# PY32.net
KiCad netlist of a schematic drawn in EasyEDA Pro
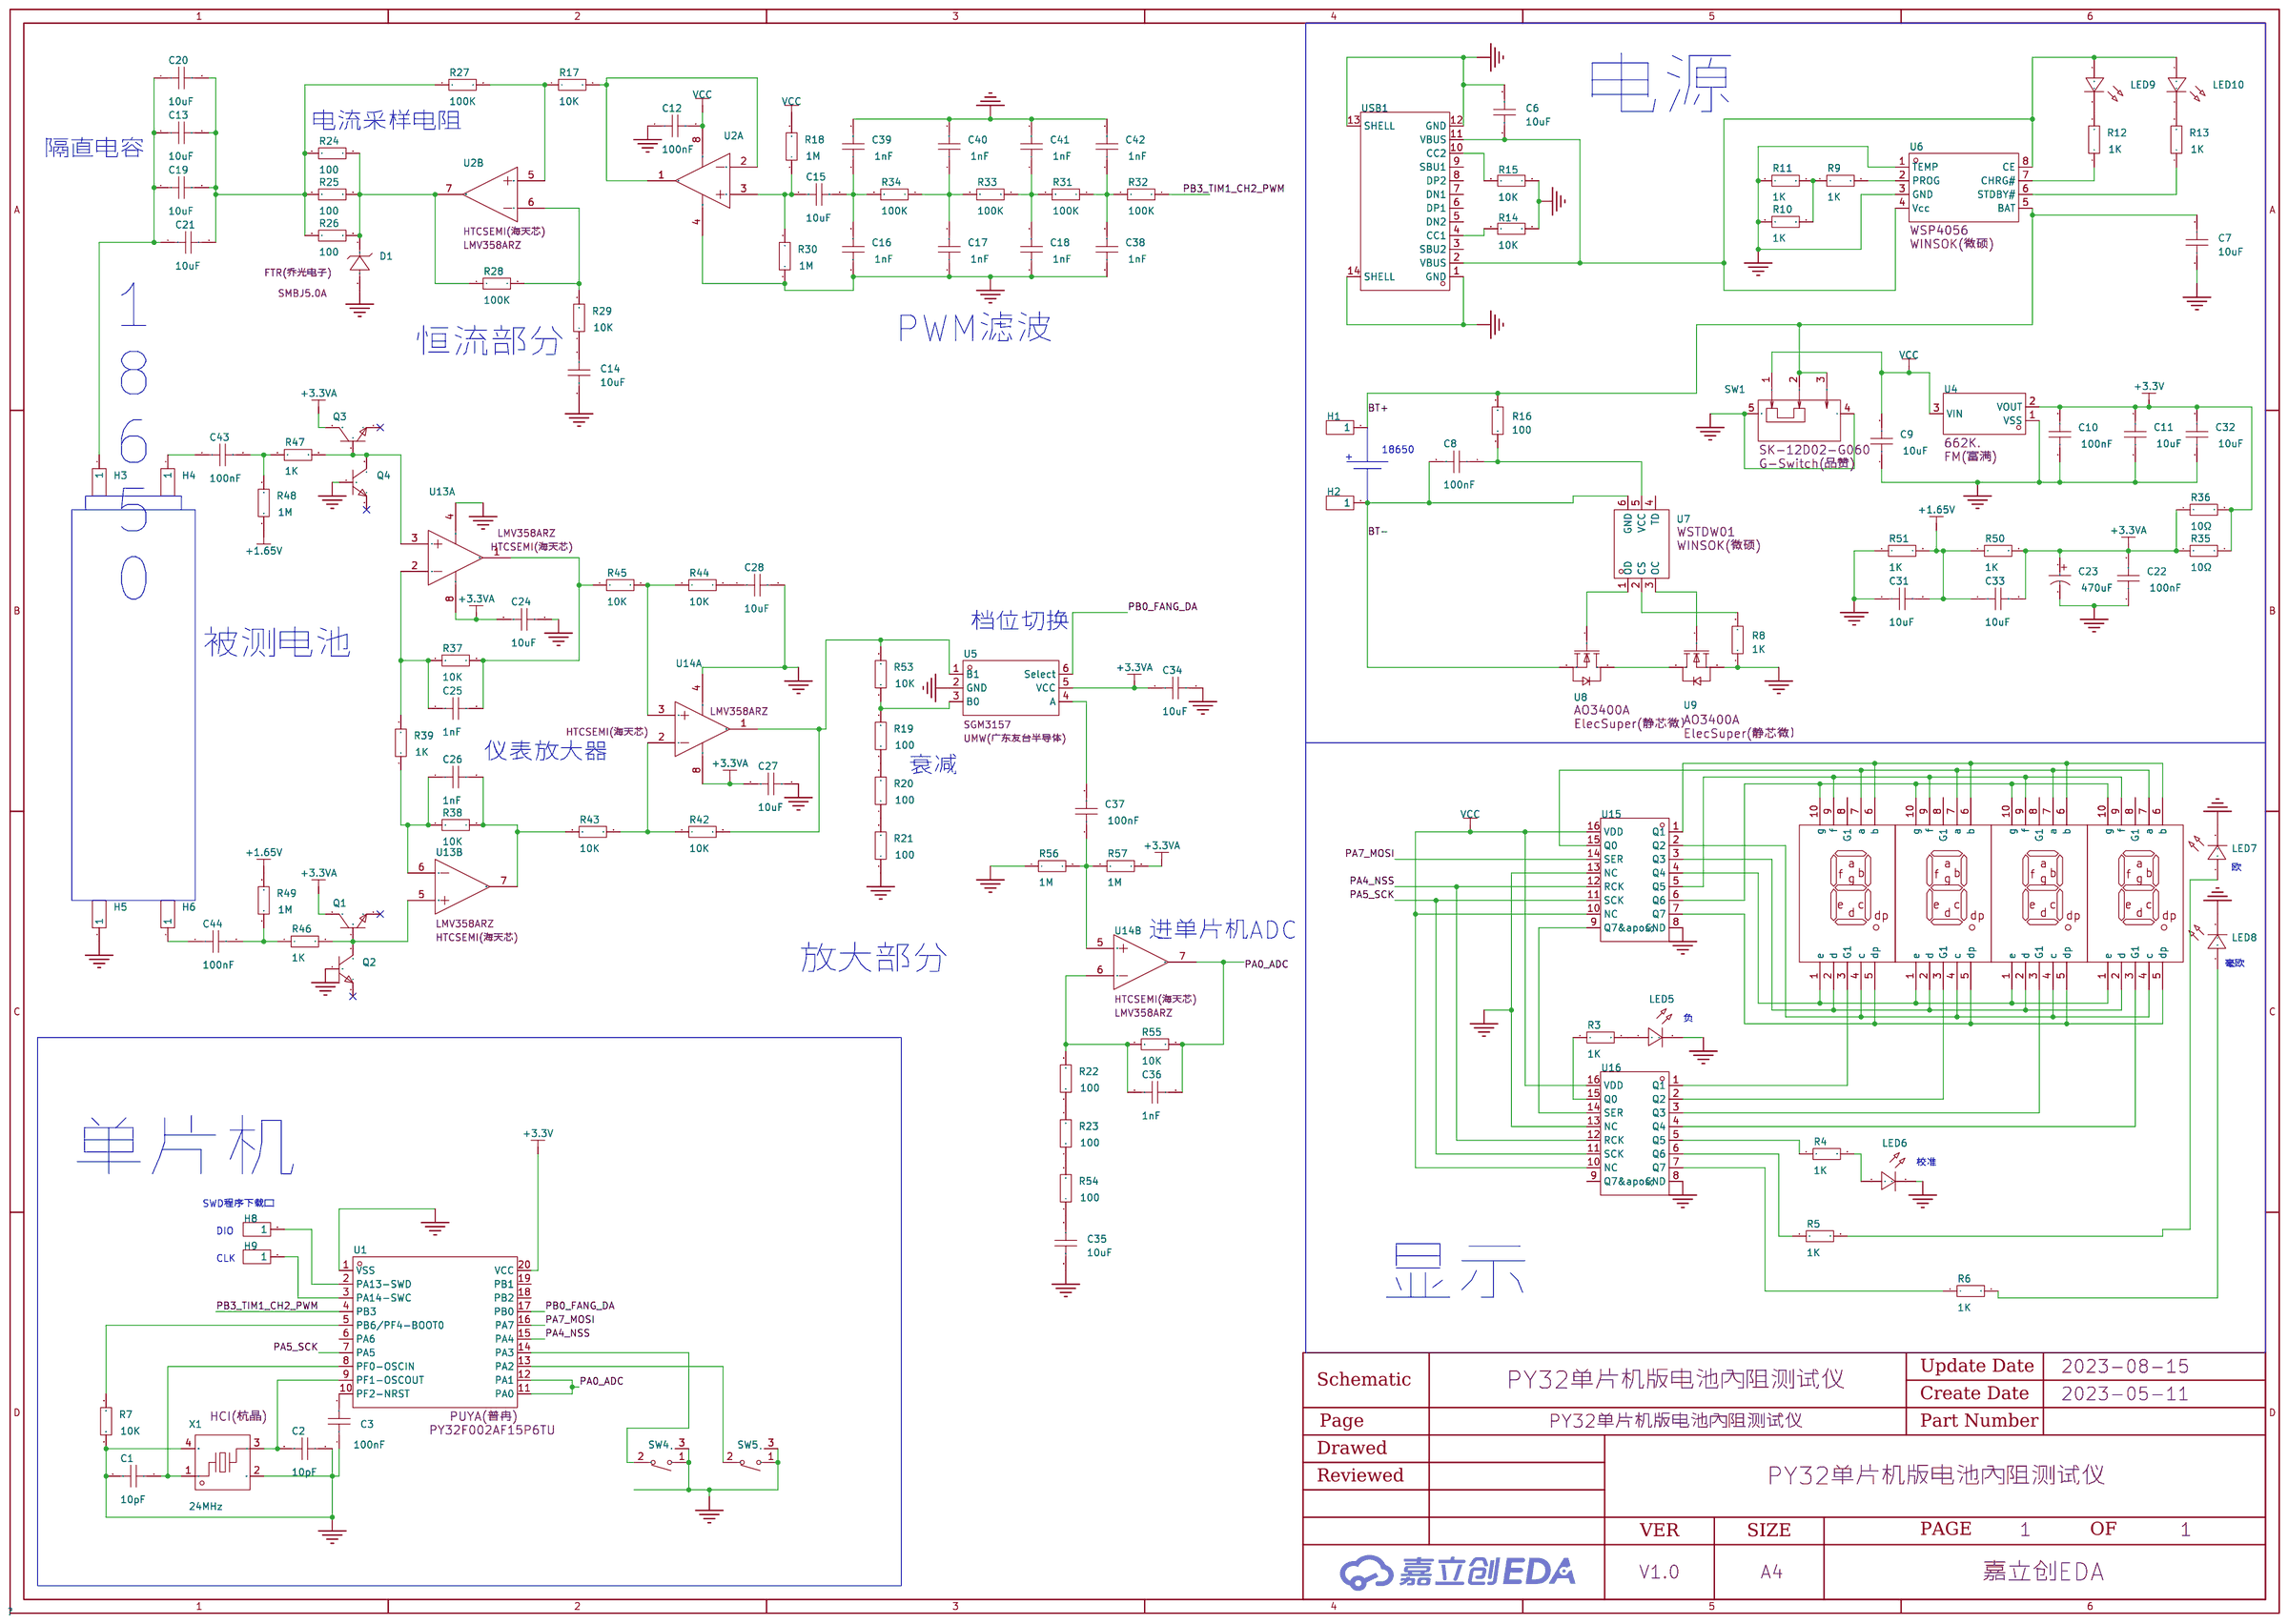
[diagram p0: schematic sheet]

(export (version "E")
  (design (tool "Eeschema 10.0.6"))
  (components
    (comp (ref "C1")
      (value "10pF")
      (footprint "easyedapro:C0603")
      (libsource (lib "easyedapro") (part "CapAcitance"))
    )
    (comp (ref "C2")
      (value "10pF")
      (footprint "easyedapro:C0603")
      (libsource (lib "easyedapro") (part "CapAcitance"))
    )
    (comp (ref "C3")
      (value "100nF")
      (footprint "easyedapro:C0603")
      (libsource (lib "easyedapro") (part "CapAcitance"))
    )
    (comp (ref "C6")
      (value "10uF")
      (footprint "easyedapro:C0603")
      (libsource (lib "easyedapro") (part "CapAcitance"))
    )
    (comp (ref "C7")
      (value "10uF")
      (footprint "easyedapro:C0603")
      (libsource (lib "easyedapro") (part "CapAcitance"))
    )
    (comp (ref "C8")
      (value "100nF")
      (footprint "easyedapro:C0603")
      (libsource (lib "easyedapro") (part "CapAcitance"))
    )
    (comp (ref "C9")
      (value "10uF")
      (footprint "easyedapro:C0603")
      (libsource (lib "easyedapro") (part "CapAcitance"))
    )
    (comp (ref "C10")
      (value "100nF")
      (footprint "easyedapro:C0603")
      (libsource (lib "easyedapro") (part "CapAcitance"))
    )
    (comp (ref "C11")
      (value "10uF")
      (footprint "easyedapro:C0603")
      (libsource (lib "easyedapro") (part "CapAcitance"))
    )
    (comp (ref "C12")
      (value "100nF")
      (footprint "easyedapro:C0603")
      (libsource (lib "easyedapro") (part "CapAcitance"))
    )
    (comp (ref "C13")
      (value "10uF")
      (footprint "easyedapro:C0603")
      (libsource (lib "easyedapro") (part "CapAcitance"))
    )
    (comp (ref "C14")
      (value "10uF")
      (footprint "easyedapro:C0603")
      (libsource (lib "easyedapro") (part "CapAcitance"))
    )
    (comp (ref "C15")
      (value "10uF")
      (footprint "easyedapro:C0603")
      (libsource (lib "easyedapro") (part "CapAcitance"))
    )
    (comp (ref "C16")
      (value "1nF")
      (footprint "easyedapro:C0603")
      (libsource (lib "easyedapro") (part "CapAcitance"))
    )
    (comp (ref "C17")
      (value "1nF")
      (footprint "easyedapro:C0603")
      (libsource (lib "easyedapro") (part "CapAcitance"))
    )
    (comp (ref "C18")
      (value "1nF")
      (footprint "easyedapro:C0603")
      (libsource (lib "easyedapro") (part "CapAcitance"))
    )
    (comp (ref "C19")
      (value "10uF")
      (footprint "easyedapro:C0603")
      (libsource (lib "easyedapro") (part "CapAcitance"))
    )
    (comp (ref "C20")
      (value "10uF")
      (footprint "easyedapro:C0603")
      (libsource (lib "easyedapro") (part "CapAcitance"))
    )
    (comp (ref "C21")
      (value "10uF")
      (footprint "easyedapro:C0603")
      (libsource (lib "easyedapro") (part "CapAcitance"))
    )
    (comp (ref "C22")
      (value "100nF")
      (footprint "easyedapro:C0603")
      (libsource (lib "easyedapro") (part "CapAcitance"))
    )
    (comp (ref "C23")
      (value "470uF")
      (footprint "easyedapro:CAP-TH_BD8.0-P3.50-D0.6-FD")
      (description "容值:470uF;精度:±20%;额定电压:16V;")
      (fields
        (field (name "Manufacturer Part") "KM477M016F12RR0VH2FP0")
        (field (name "Manufacturer") "CX(承兴)")
      )
      (libsource (lib "easyedapro") (part "470uf16v"))
    )
    (comp (ref "C24")
      (value "10uF")
      (footprint "easyedapro:C0603")
      (libsource (lib "easyedapro") (part "CapAcitance"))
    )
    (comp (ref "C25")
      (value "1nF")
      (footprint "easyedapro:C0603")
      (libsource (lib "easyedapro") (part "CapAcitance"))
    )
    (comp (ref "C26")
      (value "1nF")
      (footprint "easyedapro:C0603")
      (libsource (lib "easyedapro") (part "CapAcitance"))
    )
    (comp (ref "C27")
      (value "10uF")
      (footprint "easyedapro:C0603")
      (libsource (lib "easyedapro") (part "CapAcitance"))
    )
    (comp (ref "C28")
      (value "10uF")
      (footprint "easyedapro:C0603")
      (libsource (lib "easyedapro") (part "CapAcitance"))
    )
    (comp (ref "C31")
      (value "10uF")
      (footprint "easyedapro:C0603")
      (libsource (lib "easyedapro") (part "CapAcitance"))
    )
    (comp (ref "C32")
      (value "10uF")
      (footprint "easyedapro:C0603")
      (libsource (lib "easyedapro") (part "CapAcitance"))
    )
    (comp (ref "C33")
      (value "10uF")
      (footprint "easyedapro:C0603")
      (libsource (lib "easyedapro") (part "CapAcitance"))
    )
    (comp (ref "C34")
      (value "10uF")
      (footprint "easyedapro:C0603")
      (libsource (lib "easyedapro") (part "CapAcitance"))
    )
    (comp (ref "C35")
      (value "10uF")
      (footprint "easyedapro:C0603")
      (libsource (lib "easyedapro") (part "CapAcitance"))
    )
    (comp (ref "C36")
      (value "1nF")
      (footprint "easyedapro:C0603")
      (libsource (lib "easyedapro") (part "CapAcitance"))
    )
    (comp (ref "C37")
      (value "100nF")
      (footprint "easyedapro:C0603")
      (libsource (lib "easyedapro") (part "CapAcitance"))
    )
    (comp (ref "C38")
      (value "1nF")
      (footprint "easyedapro:C0603")
      (libsource (lib "easyedapro") (part "CapAcitance"))
    )
    (comp (ref "C39")
      (value "1nF")
      (footprint "easyedapro:C0603")
      (libsource (lib "easyedapro") (part "CapAcitance"))
    )
    (comp (ref "C40")
      (value "1nF")
      (footprint "easyedapro:C0603")
      (libsource (lib "easyedapro") (part "CapAcitance"))
    )
    (comp (ref "C41")
      (value "1nF")
      (footprint "easyedapro:C0603")
      (libsource (lib "easyedapro") (part "CapAcitance"))
    )
    (comp (ref "C42")
      (value "1nF")
      (footprint "easyedapro:C0603")
      (libsource (lib "easyedapro") (part "CapAcitance"))
    )
    (comp (ref "C43")
      (value "100nF")
      (footprint "easyedapro:C1206")
      (description "容值:100nF;精度:±10%;额定电压:450V;材质(温度系数):X7R;")
      (fields (field (name "Manufacturer Part") "FM31X104K451EEG") (field (name "Manufacturer") "PSA(信昌电陶)"))
      (libsource (lib "easyedapro") (part "FM31X104K451EEG"))
    )
    (comp (ref "C44")
      (value "100nF")
      (footprint "easyedapro:C1206")
      (description "容值:100nF;精度:±10%;额定电压:450V;材质(温度系数):X7R;")
      (fields (field (name "Manufacturer Part") "FM31X104K451EEG") (field (name "Manufacturer") "PSA(信昌电陶)"))
      (libsource (lib "easyedapro") (part "FM31X104K451EEG"))
    )
    (comp (ref "D1")
      (value "SMBJ5.0A")
      (footprint "easyedapro:SMB_L4.3-W3.6-LS5.3-RD")
      (description "极性:单向;反向截止电压(Vrwm):5V;击穿电压(最小值):6.4V;峰值脉冲电流(Ipp)@10/1000s:65.3A;最大钳位电压:9.2V;")
      (fields (field (name "Manufacturer Part") "SMBJ5.0A") (field (name "Manufacturer") "FTR(乔光电子)"))
      (libsource (lib "easyedapro") (part "SMBJ5.0A_C693503"))
    )
    (comp (ref "H1")
      (value "~")
      (footprint "easyedapro:HDR-TH_1P-V-M_XKB_X4611WV-01I-C28D40")
      (libsource (lib "easyedapro") (part "HDR_1x1"))
    )
    (comp (ref "H2")
      (value "~")
      (footprint "easyedapro:HDR-TH_1P-V-M_XKB_X4611WV-01I-C28D40")
      (libsource (lib "easyedapro") (part "HDR_1x1"))
    )
    (comp (ref "H3")
      (value "~")
      (footprint "easyedapro:HDR-TH_1P-V-M_XKB_X4611WV-01I-C28D40")
      (libsource (lib "easyedapro") (part "HDR_1x1"))
    )
    (comp (ref "H4")
      (value "~")
      (footprint "easyedapro:HDR-TH_1P-V-M_XKB_X4611WV-01I-C28D40")
      (libsource (lib "easyedapro") (part "HDR_1x1"))
    )
    (comp (ref "H5")
      (value "~")
      (footprint "easyedapro:HDR-TH_1P-V-M_XKB_X4611WV-01I-C28D40")
      (libsource (lib "easyedapro") (part "HDR_1x1"))
    )
    (comp (ref "H6")
      (value "~")
      (footprint "easyedapro:HDR-TH_1P-V-M_XKB_X4611WV-01I-C28D40")
      (libsource (lib "easyedapro") (part "HDR_1x1"))
    )
    (comp (ref "H8")
      (value "~")
      (footprint "easyedapro:HDR-TH_1P-V-M_XKB_X4611WV-01I-C28D40")
      (libsource (lib "easyedapro") (part "HDR_1x1"))
    )
    (comp (ref "H9")
      (value "~")
      (footprint "easyedapro:HDR-TH_1P-V-M_XKB_X4611WV-01I-C28D40")
      (libsource (lib "easyedapro") (part "HDR_1x1"))
    )
    (comp (ref "LED5")
      (value "~")
      (footprint "easyedapro:LED_TH-3mm")
      (libsource (lib "easyedapro") (part "LED_TH-R"))
    )
    (comp (ref "LED6")
      (value "~")
      (footprint "easyedapro:LED_TH-3mm")
      (libsource (lib "easyedapro") (part "LED_TH-R"))
    )
    (comp (ref "LED7")
      (value "~")
      (footprint "easyedapro:LED_TH-3mm")
      (libsource (lib "easyedapro") (part "LED_TH-R"))
    )
    (comp (ref "LED8")
      (value "~")
      (footprint "easyedapro:LED_TH-3mm")
      (libsource (lib "easyedapro") (part "LED_TH-R"))
    )
    (comp (ref "LED9")
      (value "~")
      (footprint "easyedapro:LED_TH-3mm")
      (libsource (lib "easyedapro") (part "LED_TH-R"))
    )
    (comp (ref "LED10")
      (value "~")
      (footprint "easyedapro:LED_TH-3mm")
      (libsource (lib "easyedapro") (part "LED_TH-R"))
    )
    (comp (ref "LED11")
      (value "SM410561N")
      (footprint "easyedapro:LED-SEG-TH_10P-L12.7-W19.0-P2.54-S15.24-BL")
      (description "数码管位数:1;数字/字母大小(英寸):0.56;LED极性:共阳;发光颜色:红色;")
      (fields (field (name "Manufacturer") "ARKLED(方舟)"))
      (libsource (lib "easyedapro") (part "SM410561N"))
    )
    (comp (ref "LED12")
      (value "SM410561N")
      (footprint "easyedapro:LED-SEG-TH_10P-L12.7-W19.0-P2.54-S15.24-BL")
      (description "数码管位数:1;数字/字母大小(英寸):0.56;LED极性:共阳;发光颜色:红色;")
      (fields (field (name "Manufacturer") "ARKLED(方舟)"))
      (libsource (lib "easyedapro") (part "SM410561N"))
    )
    (comp (ref "LED13")
      (value "SM410561N")
      (footprint "easyedapro:LED-SEG-TH_10P-L12.7-W19.0-P2.54-S15.24-BL")
      (description "数码管位数:1;数字/字母大小(英寸):0.56;LED极性:共阳;发光颜色:红色;")
      (fields (field (name "Manufacturer") "ARKLED(方舟)"))
      (libsource (lib "easyedapro") (part "SM410561N"))
    )
    (comp (ref "LED14")
      (value "SM410561N")
      (footprint "easyedapro:LED-SEG-TH_10P-L12.7-W19.0-P2.54-S15.24-BL")
      (description "数码管位数:1;数字/字母大小(英寸):0.56;LED极性:共阳;发光颜色:红色;")
      (fields (field (name "Manufacturer") "ARKLED(方舟)"))
      (libsource (lib "easyedapro") (part "SM410561N"))
    )
    (comp (ref "Q1")
      (value "SS8050")
      (footprint "easyedapro:SOT-23-3_L2.9-W1.3-P1.90-LS2.4-BR")
      (fields (field (name "Manufacturer") "ElecSuper(静芯微）"))
      (libsource (lib "easyedapro") (part "SS8050_C5249676"))
    )
    (comp (ref "Q2")
      (value "SS8050")
      (footprint "easyedapro:SOT-23-3_L2.9-W1.3-P1.90-LS2.4-BR")
      (fields (field (name "Manufacturer") "ElecSuper(静芯微）"))
      (libsource (lib "easyedapro") (part "SS8050_C5249676"))
    )
    (comp (ref "Q3")
      (value "SS8050")
      (footprint "easyedapro:SOT-23-3_L2.9-W1.3-P1.90-LS2.4-BR")
      (fields (field (name "Manufacturer") "ElecSuper(静芯微）"))
      (libsource (lib "easyedapro") (part "SS8050_C5249676"))
    )
    (comp (ref "Q4")
      (value "SS8050")
      (footprint "easyedapro:SOT-23-3_L2.9-W1.3-P1.90-LS2.4-BR")
      (fields (field (name "Manufacturer") "ElecSuper(静芯微）"))
      (libsource (lib "easyedapro") (part "SS8050_C5249676"))
    )
    (comp (ref "R3") (value "1K") (footprint "easyedapro:R0603") (libsource (lib "easyedapro") (part "电阻")))
    (comp (ref "R4") (value "1K") (footprint "easyedapro:R0603") (libsource (lib "easyedapro") (part "电阻")))
    (comp (ref "R5") (value "1K") (footprint "easyedapro:R0603") (libsource (lib "easyedapro") (part "电阻")))
    (comp (ref "R6") (value "1K") (footprint "easyedapro:R0603") (libsource (lib "easyedapro") (part "电阻")))
    (comp (ref "R7") (value "10K") (footprint "easyedapro:R0603") (libsource (lib "easyedapro") (part "电阻")))
    (comp (ref "R8") (value "1K") (footprint "easyedapro:R0603") (libsource (lib "easyedapro") (part "电阻")))
    (comp (ref "R9") (value "1K") (footprint "easyedapro:R0603") (libsource (lib "easyedapro") (part "电阻")))
    (comp (ref "R10") (value "1K") (footprint "easyedapro:R0603") (libsource (lib "easyedapro") (part "电阻")))
    (comp (ref "R11") (value "1K") (footprint "easyedapro:R0603") (libsource (lib "easyedapro") (part "电阻")))
    (comp (ref "R12") (value "1K") (footprint "easyedapro:R0603") (libsource (lib "easyedapro") (part "电阻")))
    (comp (ref "R13") (value "1K") (footprint "easyedapro:R0603") (libsource (lib "easyedapro") (part "电阻")))
    (comp (ref "R14") (value "10K") (footprint "easyedapro:R0603") (libsource (lib "easyedapro") (part "电阻")))
    (comp (ref "R15") (value "10K") (footprint "easyedapro:R0603") (libsource (lib "easyedapro") (part "电阻")))
    (comp (ref "R16") (value "100") (footprint "easyedapro:R0603") (libsource (lib "easyedapro") (part "电阻")))
    (comp (ref "R17") (value "10K") (footprint "easyedapro:R0603") (libsource (lib "easyedapro") (part "电阻")))
    (comp (ref "R18") (value "1M") (footprint "easyedapro:R0603") (libsource (lib "easyedapro") (part "电阻")))
    (comp (ref "R19") (value "100") (footprint "easyedapro:R0603") (libsource (lib "easyedapro") (part "电阻")))
    (comp (ref "R20") (value "100") (footprint "easyedapro:R0603") (libsource (lib "easyedapro") (part "电阻")))
    (comp (ref "R21") (value "100") (footprint "easyedapro:R0603") (libsource (lib "easyedapro") (part "电阻")))
    (comp (ref "R22") (value "100") (footprint "easyedapro:R0603") (libsource (lib "easyedapro") (part "电阻")))
    (comp (ref "R23") (value "100") (footprint "easyedapro:R0603") (libsource (lib "easyedapro") (part "电阻")))
    (comp (ref "R24") (value "100") (footprint "easyedapro:R0603") (libsource (lib "easyedapro") (part "电阻")))
    (comp (ref "R25") (value "100") (footprint "easyedapro:R0603") (libsource (lib "easyedapro") (part "电阻")))
    (comp (ref "R26") (value "100") (footprint "easyedapro:R0603") (libsource (lib "easyedapro") (part "电阻")))
    (comp (ref "R27")
      (value "100K")
      (footprint "easyedapro:R0603")
      (libsource (lib "easyedapro") (part "电阻"))
    )
    (comp (ref "R28")
      (value "100K")
      (footprint "easyedapro:R0603")
      (libsource (lib "easyedapro") (part "电阻"))
    )
    (comp (ref "R29") (value "10K") (footprint "easyedapro:R0603") (libsource (lib "easyedapro") (part "电阻")))
    (comp (ref "R30") (value "1M") (footprint "easyedapro:R0603") (libsource (lib "easyedapro") (part "电阻")))
    (comp (ref "R31")
      (value "100K")
      (footprint "easyedapro:R0603")
      (libsource (lib "easyedapro") (part "电阻"))
    )
    (comp (ref "R32")
      (value "100K")
      (footprint "easyedapro:R0603")
      (libsource (lib "easyedapro") (part "电阻"))
    )
    (comp (ref "R33")
      (value "100K")
      (footprint "easyedapro:R0603")
      (libsource (lib "easyedapro") (part "电阻"))
    )
    (comp (ref "R34")
      (value "100K")
      (footprint "easyedapro:R0603")
      (libsource (lib "easyedapro") (part "电阻"))
    )
    (comp (ref "R35") (value "10Ω") (footprint "easyedapro:R0603") (libsource (lib "easyedapro") (part "电阻")))
    (comp (ref "R36") (value "10Ω") (footprint "easyedapro:R0603") (libsource (lib "easyedapro") (part "电阻")))
    (comp (ref "R37") (value "10K") (footprint "easyedapro:R0603") (libsource (lib "easyedapro") (part "电阻")))
    (comp (ref "R38") (value "10K") (footprint "easyedapro:R0603") (libsource (lib "easyedapro") (part "电阻")))
    (comp (ref "R39") (value "1K") (footprint "easyedapro:R0603") (libsource (lib "easyedapro") (part "电阻")))
    (comp (ref "R42") (value "10K") (footprint "easyedapro:R0603") (libsource (lib "easyedapro") (part "电阻")))
    (comp (ref "R43") (value "10K") (footprint "easyedapro:R0603") (libsource (lib "easyedapro") (part "电阻")))
    (comp (ref "R44") (value "10K") (footprint "easyedapro:R0603") (libsource (lib "easyedapro") (part "电阻")))
    (comp (ref "R45") (value "10K") (footprint "easyedapro:R0603") (libsource (lib "easyedapro") (part "电阻")))
    (comp (ref "R46") (value "1K") (footprint "easyedapro:R0603") (libsource (lib "easyedapro") (part "电阻")))
    (comp (ref "R47") (value "1K") (footprint "easyedapro:R0603") (libsource (lib "easyedapro") (part "电阻")))
    (comp (ref "R48") (value "1M") (footprint "easyedapro:R0603") (libsource (lib "easyedapro") (part "电阻")))
    (comp (ref "R49") (value "1M") (footprint "easyedapro:R0603") (libsource (lib "easyedapro") (part "电阻")))
    (comp (ref "R50") (value "1K") (footprint "easyedapro:R0603") (libsource (lib "easyedapro") (part "电阻")))
    (comp (ref "R51") (value "1K") (footprint "easyedapro:R0603") (libsource (lib "easyedapro") (part "电阻")))
    (comp (ref "R53") (value "10K") (footprint "easyedapro:R0603") (libsource (lib "easyedapro") (part "电阻")))
    (comp (ref "R54") (value "100") (footprint "easyedapro:R0603") (libsource (lib "easyedapro") (part "电阻")))
    (comp (ref "R55") (value "10K") (footprint "easyedapro:R0603") (libsource (lib "easyedapro") (part "电阻")))
    (comp (ref "R56") (value "1M") (footprint "easyedapro:R0603") (libsource (lib "easyedapro") (part "电阻")))
    (comp (ref "R57") (value "1M") (footprint "easyedapro:R0603") (libsource (lib "easyedapro") (part "电阻")))
    (comp (ref "SW1")
      (value "SK-12D02-G060")
      (footprint "easyedapro:SW-TH_SK-12D02-G060")
      (description "额定电流(DC):1A;额定电压(DC):24V;电路结构:单刀双掷;安装方式:卧插;机械寿命:1万次;开关颜色:黑色;")
      (fields (field (name "Manufacturer Part") "SK-12D02-G060") (field (name "Manufacturer") "G-Switch(品赞)"))
      (libsource (lib "easyedapro") (part "SK-12D02-G060"))
    )
    (comp (ref "SW4")
      (value "HX TS4538B3J 250gf")
      (footprint "easyedapro:SW-TH_TS4538B3J")
      (description "机械寿命:-;")
      (fields (field (name "Manufacturer") "hanxia(韩下)"))
      (libsource (lib "easyedapro") (part "HX TS4538B3J 250GF"))
    )
    (comp (ref "SW5")
      (value "HX TS4538B3J 250gf")
      (footprint "easyedapro:SW-TH_TS4538B3J")
      (description "机械寿命:-;")
      (fields (field (name "Manufacturer") "hanxia(韩下)"))
      (libsource (lib "easyedapro") (part "HX TS4538B3J 250GF"))
    )
    (comp (ref "U1")
      (value "PY32F002AF15P6TU")
      (footprint "easyedapro:TSSOP-20_L6.5-W4.4-P0.65-LS6.4-BL")
      (fields (field (name "Manufacturer Part") "PY32F002AF15P6TU") (field (name "Manufacturer") "PUYA(普冉)"))
      (libsource (lib "easyedapro") (part "PY32F002AF15P6TU"))
    )
    (comp (ref "U2")
      (value "LMV358ARZ")
      (footprint "easyedapro:SOP-8_L4.9-W3.9-P1.27-LS6.0-BL")
      (description "CMOS低功耗双路运算放大器")
      (fields (field (name "Manufacturer") "HTCSEMI(海天芯)") (field (name "Manufacturer Part") "LMV358ARZ"))
      (libsource (lib "easyedapro") (part "LMV358ARZ"))
    )
    (comp (ref "U4")
      (value "662K.")
      (footprint "easyedapro:SOT-23-3_L2.9-W1.3-P1.90-LS2.4-BR")
      (description "输出类型:-;")
      (fields (field (name "Manufacturer Part") "662K.") (field (name "Manufacturer") "FM(富满)"))
      (libsource (lib "easyedapro") (part "662K."))
    )
    (comp (ref "U5")
      (value "SGM3157")
      (footprint "easyedapro:SC-70-6_L2.2-W1.3-P0.65-LS2.1-BL")
      (description "开关电路:-;")
      (fields (field (name "Manufacturer Part") "SGM3157") (field (name "Manufacturer") "UMW(广东友台半导体)"))
      (libsource (lib "easyedapro") (part "SGM3157"))
    )
    (comp (ref "U6")
      (value "WSP4056")
      (footprint "easyedapro:SOP-8_L5.1-W3.9-P1.27-LS6.0-BL")
      (fields (field (name "Manufacturer Part") "WSP4056") (field (name "Manufacturer") "WINSOK(微硕)"))
      (libsource (lib "easyedapro") (part "WSP4056"))
    )
    (comp (ref "U7")
      (value "WSTDW01")
      (footprint "easyedapro:SOT-23-6_L2.9-W1.6-P0.95-LS2.8-BR")
      (description "充电电池的类型:-;电池单元组数:-;最大充电电流:-;充满的电池组电压:-;最大供应电压:-;")
      (fields (field (name "Manufacturer Part") "WSTDW01") (field (name "Manufacturer") "WINSOK(微硕)"))
      (libsource (lib "easyedapro") (part "WSTDW01"))
    )
    (comp (ref "U8")
      (value "AO3400A")
      (footprint "easyedapro:SOT-23-3_L3.0-W1.6-P1.90-LS2.8-BR")
      (description "类型:N沟道;漏源电压(Vdss):30V;连续漏极电流(Id):6A;功率(Pd):1.4W;导通电阻(RDS(on)@Vgs,Id):19mΩ@10V,6.0A;")
      (fields (field (name "Manufacturer Part") "AO3400A") (field (name "Manufacturer") "ElecSuper(静芯微）"))
      (libsource (lib "easyedapro") (part "AO3400A_C5224194"))
    )
    (comp (ref "U9")
      (value "AO3400A")
      (footprint "easyedapro:SOT-23-3_L3.0-W1.6-P1.90-LS2.8-BR")
      (description "类型:N沟道;漏源电压(Vdss):30V;连续漏极电流(Id):6A;功率(Pd):1.4W;导通电阻(RDS(on)@Vgs,Id):19mΩ@10V,6.0A;")
      (fields (field (name "Manufacturer Part") "AO3400A") (field (name "Manufacturer") "ElecSuper(静芯微）"))
      (libsource (lib "easyedapro") (part "AO3400A_C5224194"))
    )
    (comp (ref "U13")
      (value "LMV358ARZ")
      (footprint "easyedapro:SOP-8_L4.9-W3.9-P1.27-LS6.0-BL")
      (description "CMOS低功耗双路运算放大器")
      (fields (field (name "Manufacturer Part") "LMV358ARZ") (field (name "Manufacturer") "HTCSEMI(海天芯)"))
      (libsource (lib "easyedapro") (part "LMV358ARZ"))
    )
    (comp (ref "U14")
      (value "LMV358ARZ")
      (footprint "easyedapro:SOP-8_L4.9-W3.9-P1.27-LS6.0-BL")
      (description "CMOS低功耗双路运算放大器")
      (fields (field (name "Manufacturer Part") "LMV358ARZ") (field (name "Manufacturer") "HTCSEMI(海天芯)"))
      (libsource (lib "easyedapro") (part "LMV358ARZ"))
    )
    (comp (ref "U15")
      (value "74HC595D.")
      (footprint "easyedapro:SOP-16_L9.9-W3.9-P1.27-LS6.0-BL")
      (fields (field (name "Manufacturer") "FM(富满)"))
      (libsource (lib "easyedapro") (part "74HC595D."))
    )
    (comp (ref "U16")
      (value "74HC595D.")
      (footprint "easyedapro:SOP-16_L9.9-W3.9-P1.27-LS6.0-BL")
      (fields (field (name "Manufacturer") "FM(富满)"))
      (libsource (lib "easyedapro") (part "74HC595D."))
    )
    (comp (ref "USB1")
      (value "TYPE-C 16PIN 2MD(073)")
      (footprint "easyedapro:USB-C-SMD_TYPE-C-6PIN-2MD-073")
      (description "连接器类型:Type-C;标准:-;公母:母座;触点数量:16;端口数量:1;安装方式:卧贴;额定电流 - 电源:5A;工作温度范围:-25°C~+85°C;")
      (fields (field (name "Manufacturer") "SHOU HAN(首韩)"))
      (libsource (lib "easyedapro") (part "TYPE-C 16PIN 2MD(073)"))
    )
    (comp (ref "X1")
      (value "24MHz")
      (footprint "easyedapro:CRYSTAL-SMD_4P-L3.2-W2.5-BL")
      (description "频率:24MHz;频率公差:±10ppm;频率稳定度:±30ppm;负载电容:12pF;")
      (fields
        (field (name "Manufacturer Part") "XC32M4-24.000-F12NJDTL")
        (field (name "Manufacturer") "HCI(杭晶)")
      )
      (libsource (lib "easyedapro") (part "XC32M4-24.000-F12NJDTL"))
    )
  )
  (nets
    (net (code "1") (name "+1.65V") (class "Default")
      (node (ref "C31") (pin "2") (pinfunction "2_2") (pintype "input"))
      (node (ref "C33") (pin "1") (pinfunction "1_1") (pintype "input"))
      (node (ref "R48") (pin "1") (pinfunction "1_1") (pintype "input"))
      (node (ref "R49") (pin "2") (pinfunction "2_2") (pintype "input"))
      (node (ref "R50") (pin "1") (pinfunction "1_1") (pintype "input"))
      (node (ref "R51") (pin "2") (pinfunction "2_2") (pintype "input"))
    )
    (net (code "2") (name "+3.3V") (class "Default")
      (node (ref "C10") (pin "2") (pinfunction "2_2") (pintype "input"))
      (node (ref "C11") (pin "2") (pinfunction "2_2") (pintype "input"))
      (node (ref "C32") (pin "2") (pinfunction "2_2") (pintype "input"))
      (node (ref "R35") (pin "2") (pinfunction "2_2") (pintype "input"))
      (node (ref "R36") (pin "2") (pinfunction "2_2") (pintype "input"))
      (node (ref "U1") (pin "20") (pinfunction "VCC_20") (pintype "input"))
      (node (ref "U4") (pin "2") (pinfunction "VOUT_2") (pintype "input"))
    )
    (net (code "3") (name "+3.3VA") (class "Default")
      (node (ref "C22") (pin "2") (pinfunction "2_2") (pintype "input"))
      (node (ref "C23") (pin "1") (pinfunction "1_1") (pintype "input"))
      (node (ref "C24") (pin "2") (pinfunction "2_2") (pintype "input"))
      (node (ref "C27") (pin "1") (pinfunction "1_1") (pintype "input"))
      (node (ref "C33") (pin "2") (pinfunction "2_2") (pintype "input"))
      (node (ref "C34") (pin "1") (pinfunction "1_1") (pintype "input"))
      (node (ref "Q1") (pin "3") (pinfunction "C_3") (pintype "input"))
      (node (ref "Q3") (pin "3") (pinfunction "C_3") (pintype "input"))
      (node (ref "R35") (pin "1") (pinfunction "1_1") (pintype "input"))
      (node (ref "R36") (pin "1") (pinfunction "1_1") (pintype "input"))
      (node (ref "R50") (pin "2") (pinfunction "2_2") (pintype "input"))
      (node (ref "R57") (pin "2") (pinfunction "2_2") (pintype "input"))
      (node (ref "U13") (pin "8") (pinfunction "VCC_8") (pintype "input"))
      (node (ref "U14") (pin "8") (pinfunction "VCC_8") (pintype "input"))
      (node (ref "U5") (pin "5") (pinfunction "VCC_5") (pintype "input"))
    )
    (net (code "4") (name "/BT+") (class "Default")
      (node (ref "C7") (pin "2") (pinfunction "2_2") (pintype "input"))
      (node (ref "H1") (pin "1") (pinfunction "1_1") (pintype "unspecified"))
      (node (ref "R16") (pin "2") (pinfunction "2_2") (pintype "input"))
      (node (ref "SW1") (pin "2") (pinfunction "2_2") (pintype "input"))
      (node (ref "SW1") (pin "3") (pinfunction "3_3") (pintype "input"))
      (node (ref "U6") (pin "5") (pinfunction "BAT_5") (pintype "input"))
    )
    (net (code "5") (name "/BT-") (class "Default")
      (node (ref "C8") (pin "2") (pinfunction "2_2") (pintype "input"))
      (node (ref "H2") (pin "1") (pinfunction "1_1") (pintype "unspecified"))
      (node (ref "U7") (pin "6") (pinfunction "GND_6") (pintype "input"))
      (node (ref "U8") (pin "2") (pinfunction "S_2") (pintype "input"))
    )
    (net (code "6") (name "/PA0_ADC") (class "Default")
      (node (ref "C36") (pin "2") (pinfunction "2_2") (pintype "input"))
      (node (ref "R55") (pin "2") (pinfunction "2_2") (pintype "input"))
      (node (ref "U1") (pin "11") (pinfunction "PA0_11") (pintype "input"))
      (node (ref "U1") (pin "12") (pinfunction "PA1_12") (pintype "input"))
      (node (ref "U14") (pin "7") (pinfunction "OUT2_7") (pintype "output"))
    )
    (net (code "7") (name "/PA4_NSS") (class "Default")
      (node (ref "U1") (pin "15") (pinfunction "PA4_15") (pintype "input"))
      (node (ref "U15") (pin "12") (pinfunction "RCK_12") (pintype "input"))
      (node (ref "U16") (pin "12") (pinfunction "RCK_12") (pintype "input"))
    )
    (net (code "8") (name "/PA5_SCK") (class "Default")
      (node (ref "U1") (pin "7") (pinfunction "PA5_7") (pintype "input"))
      (node (ref "U15") (pin "11") (pinfunction "SCK_11") (pintype "input"))
      (node (ref "U16") (pin "11") (pinfunction "SCK_11") (pintype "input"))
    )
    (net (code "9") (name "/PA7_MOSI") (class "Default")
      (node (ref "U1") (pin "16") (pinfunction "PA7_16") (pintype "input"))
      (node (ref "U15") (pin "14") (pinfunction "SER_14") (pintype "input"))
    )
    (net (code "10") (name "/PB0_FANG_DA") (class "Default")
      (node (ref "U1") (pin "17") (pinfunction "PB0_17") (pintype "input"))
      (node (ref "U5") (pin "6") (pinfunction "Select_6") (pintype "input"))
    )
    (net (code "11") (name "/PB3_TIM1_CH2_PWM") (class "Default")
      (node (ref "R32") (pin "1") (pinfunction "1_1") (pintype "input"))
      (node (ref "U1") (pin "4") (pinfunction "PB3_4") (pintype "input"))
    )
    (net (code "12") (name "GND") (class "Default")
      (node (ref "C1") (pin "2") (pinfunction "2_2") (pintype "input"))
      (node (ref "C10") (pin "1") (pinfunction "1_1") (pintype "input"))
      (node (ref "C11") (pin "1") (pinfunction "1_1") (pintype "input"))
      (node (ref "C12") (pin "1") (pinfunction "1_1") (pintype "input"))
      (node (ref "C14") (pin "1") (pinfunction "1_1") (pintype "input"))
      (node (ref "C16") (pin "1") (pinfunction "1_1") (pintype "input"))
      (node (ref "C17") (pin "1") (pinfunction "1_1") (pintype "input"))
      (node (ref "C18") (pin "1") (pinfunction "1_1") (pintype "input"))
      (node (ref "C2") (pin "1") (pinfunction "1_1") (pintype "input"))
      (node (ref "C22") (pin "1") (pinfunction "1_1") (pintype "input"))
      (node (ref "C23") (pin "2") (pinfunction "2_2") (pintype "input"))
      (node (ref "C24") (pin "1") (pinfunction "1_1") (pintype "input"))
      (node (ref "C27") (pin "2") (pinfunction "2_2") (pintype "input"))
      (node (ref "C28") (pin "2") (pinfunction "2_2") (pintype "input"))
      (node (ref "C3") (pin "1") (pinfunction "1_1") (pintype "input"))
      (node (ref "C31") (pin "1") (pinfunction "1_1") (pintype "input"))
      (node (ref "C32") (pin "1") (pinfunction "1_1") (pintype "input"))
      (node (ref "C34") (pin "2") (pinfunction "2_2") (pintype "input"))
      (node (ref "C35") (pin "1") (pinfunction "1_1") (pintype "input"))
      (node (ref "C38") (pin "1") (pinfunction "1_1") (pintype "input"))
      (node (ref "C39") (pin "2") (pinfunction "2_2") (pintype "input"))
      (node (ref "C40") (pin "2") (pinfunction "2_2") (pintype "input"))
      (node (ref "C41") (pin "2") (pinfunction "2_2") (pintype "input"))
      (node (ref "C42") (pin "2") (pinfunction "2_2") (pintype "input"))
      (node (ref "C6") (pin "2") (pinfunction "2_2") (pintype "input"))
      (node (ref "C7") (pin "1") (pinfunction "1_1") (pintype "input"))
      (node (ref "C9") (pin "1") (pinfunction "1_1") (pintype "input"))
      (node (ref "D1") (pin "2") (pinfunction "A_2") (pintype "input"))
      (node (ref "H5") (pin "1") (pinfunction "1_1") (pintype "unspecified"))
      (node (ref "LED5") (pin "2") (pinfunction "A_2") (pintype "input"))
      (node (ref "LED6") (pin "2") (pinfunction "A_2") (pintype "input"))
      (node (ref "LED7") (pin "2") (pinfunction "A_2") (pintype "input"))
      (node (ref "LED8") (pin "2") (pinfunction "A_2") (pintype "input"))
      (node (ref "Q2") (pin "1") (pinfunction "B_1") (pintype "input"))
      (node (ref "Q4") (pin "1") (pinfunction "B_1") (pintype "input"))
      (node (ref "R10") (pin "1") (pinfunction "1_1") (pintype "input"))
      (node (ref "R11") (pin "1") (pinfunction "1_1") (pintype "input"))
      (node (ref "R14") (pin "1") (pinfunction "1_1") (pintype "input"))
      (node (ref "R15") (pin "1") (pinfunction "1_1") (pintype "input"))
      (node (ref "R21") (pin "1") (pinfunction "1_1") (pintype "input"))
      (node (ref "R30") (pin "1") (pinfunction "1_1") (pintype "input"))
      (node (ref "R51") (pin "1") (pinfunction "1_1") (pintype "input"))
      (node (ref "R56") (pin "1") (pinfunction "1_1") (pintype "input"))
      (node (ref "R7") (pin "1") (pinfunction "1_1") (pintype "input"))
      (node (ref "R8") (pin "1") (pinfunction "1_1") (pintype "input"))
      (node (ref "SW1") (pin "4") (pinfunction "4_4") (pintype "input"))
      (node (ref "SW1") (pin "5") (pinfunction "5_5") (pintype "input"))
      (node (ref "SW4") (pin "1") (pinfunction "1_1") (pintype "input"))
      (node (ref "SW4") (pin "3") (pinfunction "3_3") (pintype "input"))
      (node (ref "SW5") (pin "1") (pinfunction "1_1") (pintype "input"))
      (node (ref "SW5") (pin "3") (pinfunction "3_3") (pintype "input"))
      (node (ref "U1") (pin "1") (pinfunction "VSS_1") (pintype "input"))
      (node (ref "U13") (pin "4") (pinfunction "GND_4") (pintype "input"))
      (node (ref "U14") (pin "4") (pinfunction "GND_4") (pintype "input"))
      (node (ref "U15") (pin "13") (pinfunction "NC_13") (pintype "input"))
      (node (ref "U15") (pin "8") (pinfunction "GND_8") (pintype "input"))
      (node (ref "U16") (pin "13") (pinfunction "NC_13") (pintype "input"))
      (node (ref "U16") (pin "8") (pinfunction "GND_8") (pintype "input"))
      (node (ref "U2") (pin "4") (pinfunction "GND_4") (pintype "input"))
      (node (ref "U4") (pin "1") (pinfunction "VSS_1") (pintype "input"))
      (node (ref "U5") (pin "2") (pinfunction "GND_2") (pintype "input"))
      (node (ref "U6") (pin "1") (pinfunction "TEMP_1") (pintype "input"))
      (node (ref "U6") (pin "3") (pinfunction "GND_3") (pintype "input"))
      (node (ref "U9") (pin "2") (pinfunction "S_2") (pintype "input"))
      (node (ref "USB1") (pin "1") (pinfunction "GND_1") (pintype "input"))
      (node (ref "USB1") (pin "12") (pinfunction "GND_12") (pintype "input"))
      (node (ref "USB1") (pin "13") (pinfunction "SHELL_13") (pintype "input"))
      (node (ref "USB1") (pin "14") (pinfunction "SHELL_14") (pintype "input"))
      (node (ref "X1") (pin "2") (pinfunction "GND_2") (pintype "input"))
      (node (ref "X1") (pin "4") (pinfunction "GND_4") (pintype "input"))
    )
    (net (code "13") (name "Net-(C13-Pad1)") (class "Default")
      (node (ref "C13") (pin "1") (pinfunction "1_1") (pintype "input"))
      (node (ref "C19") (pin "1") (pinfunction "1_1") (pintype "input"))
      (node (ref "C20") (pin "1") (pinfunction "1_1") (pintype "input"))
      (node (ref "C21") (pin "1") (pinfunction "1_1") (pintype "input"))
      (node (ref "H3") (pin "1") (pinfunction "1_1") (pintype "unspecified"))
    )
    (net (code "14") (name "Net-(C13-Pad2)") (class "Default")
      (node (ref "C13") (pin "2") (pinfunction "2_2") (pintype "input"))
      (node (ref "C19") (pin "2") (pinfunction "2_2") (pintype "input"))
      (node (ref "C20") (pin "2") (pinfunction "2_2") (pintype "input"))
      (node (ref "C21") (pin "2") (pinfunction "2_2") (pintype "input"))
      (node (ref "R24") (pin "1") (pinfunction "1_1") (pintype "input"))
      (node (ref "R25") (pin "1") (pinfunction "1_1") (pintype "input"))
      (node (ref "R26") (pin "1") (pinfunction "1_1") (pintype "input"))
      (node (ref "R27") (pin "1") (pinfunction "1_1") (pintype "input"))
    )
    (net (code "15") (name "Net-(C14-Pad2)") (class "Default")
      (node (ref "C14") (pin "2") (pinfunction "2_2") (pintype "input"))
      (node (ref "R29") (pin "1") (pinfunction "1_1") (pintype "input"))
    )
    (net (code "16") (name "Net-(C15-Pad2)") (class "Default")
      (node (ref "C15") (pin "2") (pinfunction "2_2") (pintype "input"))
      (node (ref "C16") (pin "2") (pinfunction "2_2") (pintype "input"))
      (node (ref "C39") (pin "1") (pinfunction "1_1") (pintype "input"))
      (node (ref "R34") (pin "2") (pinfunction "2_2") (pintype "input"))
    )
    (net (code "17") (name "Net-(C17-Pad2)") (class "Default")
      (node (ref "C17") (pin "2") (pinfunction "2_2") (pintype "input"))
      (node (ref "C40") (pin "1") (pinfunction "1_1") (pintype "input"))
      (node (ref "R33") (pin "2") (pinfunction "2_2") (pintype "input"))
      (node (ref "R34") (pin "1") (pinfunction "1_1") (pintype "input"))
    )
    (net (code "18") (name "Net-(C18-Pad2)") (class "Default")
      (node (ref "C18") (pin "2") (pinfunction "2_2") (pintype "input"))
      (node (ref "C41") (pin "1") (pinfunction "1_1") (pintype "input"))
      (node (ref "R31") (pin "2") (pinfunction "2_2") (pintype "input"))
      (node (ref "R33") (pin "1") (pinfunction "1_1") (pintype "input"))
    )
    (net (code "19") (name "Net-(C28-Pad1)") (class "Default")
      (node (ref "C28") (pin "1") (pinfunction "1_1") (pintype "input"))
      (node (ref "R44") (pin "2") (pinfunction "2_2") (pintype "input"))
    )
    (net (code "20") (name "Net-(C35-Pad2)") (class "Default")
      (node (ref "C35") (pin "2") (pinfunction "2_2") (pintype "input"))
      (node (ref "R54") (pin "1") (pinfunction "1_1") (pintype "input"))
    )
    (net (code "21") (name "Net-(C38-Pad2)") (class "Default")
      (node (ref "C38") (pin "2") (pinfunction "2_2") (pintype "input"))
      (node (ref "C42") (pin "1") (pinfunction "1_1") (pintype "input"))
      (node (ref "R31") (pin "1") (pinfunction "1_1") (pintype "input"))
      (node (ref "R32") (pin "2") (pinfunction "2_2") (pintype "input"))
    )
    (net (code "22") (name "Net-(C43-Pad1)") (class "Default")
      (node (ref "C43") (pin "1") (pinfunction "1_1") (pintype "input"))
      (node (ref "H4") (pin "1") (pinfunction "1_1") (pintype "unspecified"))
    )
    (net (code "23") (name "Net-(C43-Pad2)") (class "Default")
      (node (ref "C43") (pin "2") (pinfunction "2_2") (pintype "input"))
      (node (ref "R47") (pin "1") (pinfunction "1_1") (pintype "input"))
      (node (ref "R48") (pin "2") (pinfunction "2_2") (pintype "input"))
    )
    (net (code "24") (name "Net-(C44-Pad1)") (class "Default")
      (node (ref "C44") (pin "1") (pinfunction "1_1") (pintype "input"))
      (node (ref "H6") (pin "1") (pinfunction "1_1") (pintype "unspecified"))
    )
    (net (code "25") (name "Net-(C44-Pad2)") (class "Default")
      (node (ref "C44") (pin "2") (pinfunction "2_2") (pintype "input"))
      (node (ref "R46") (pin "1") (pinfunction "1_1") (pintype "input"))
      (node (ref "R49") (pin "1") (pinfunction "1_1") (pintype "input"))
    )
    (net (code "26") (name "Net-(D1-C)") (class "Default")
      (node (ref "D1") (pin "1") (pinfunction "C_1") (pintype "input"))
      (node (ref "R24") (pin "2") (pinfunction "2_2") (pintype "input"))
      (node (ref "R25") (pin "2") (pinfunction "2_2") (pintype "input"))
      (node (ref "R26") (pin "2") (pinfunction "2_2") (pintype "input"))
      (node (ref "R28") (pin "1") (pinfunction "1_1") (pintype "input"))
      (node (ref "U2") (pin "7") (pinfunction "OUT2_7") (pintype "output"))
    )
    (net (code "27") (name "Net-(LED5-C)") (class "Default")
      (node (ref "LED5") (pin "1") (pinfunction "C_1") (pintype "input"))
      (node (ref "R3") (pin "2") (pinfunction "2_2") (pintype "input"))
    )
    (net (code "28") (name "Net-(LED6-C)") (class "Default")
      (node (ref "LED6") (pin "1") (pinfunction "C_1") (pintype "input"))
      (node (ref "R4") (pin "2") (pinfunction "2_2") (pintype "input"))
    )
    (net (code "29") (name "Net-(LED7-C)") (class "Default")
      (node (ref "LED7") (pin "1") (pinfunction "C_1") (pintype "input"))
      (node (ref "R5") (pin "2") (pinfunction "2_2") (pintype "input"))
    )
    (net (code "30") (name "Net-(LED8-C)") (class "Default")
      (node (ref "LED8") (pin "1") (pinfunction "C_1") (pintype "input"))
      (node (ref "R6") (pin "2") (pinfunction "2_2") (pintype "input"))
    )
    (net (code "31") (name "Net-(LED9-A)") (class "Default")
      (node (ref "LED9") (pin "2") (pinfunction "A_2") (pintype "input"))
      (node (ref "R12") (pin "2") (pinfunction "2_2") (pintype "input"))
    )
    (net (code "32") (name "Net-(LED10-A)") (class "Default")
      (node (ref "LED10") (pin "2") (pinfunction "A_2") (pintype "input"))
      (node (ref "R13") (pin "2") (pinfunction "2_2") (pintype "input"))
    )
    (net (code "33") (name "Net-(LED10-C)") (class "Default")
      (node (ref "C6") (pin "1") (pinfunction "1_1") (pintype "input"))
      (node (ref "LED10") (pin "1") (pinfunction "C_1") (pintype "input"))
      (node (ref "LED9") (pin "1") (pinfunction "C_1") (pintype "input"))
      (node (ref "U6") (pin "4") (pinfunction "Vcc_4") (pintype "input"))
      (node (ref "U6") (pin "8") (pinfunction "CE_8") (pintype "input"))
      (node (ref "USB1") (pin "11") (pinfunction "VBUS_11") (pintype "input"))
      (node (ref "USB1") (pin "2") (pinfunction "VBUS_2") (pintype "input"))
    )
    (net (code "34") (name "Net-(LED11-a)") (class "Default")
      (node (ref "LED11") (pin "7") (pinfunction "a_7") (pintype "input"))
      (node (ref "LED12") (pin "7") (pinfunction "a_7") (pintype "input"))
      (node (ref "LED13") (pin "7") (pinfunction "a_7") (pintype "input"))
      (node (ref "LED14") (pin "7") (pinfunction "a_7") (pintype "input"))
      (node (ref "U15") (pin "15") (pinfunction "Q0_15") (pintype "input"))
    )
    (net (code "35") (name "Net-(LED11-b)") (class "Default")
      (node (ref "LED11") (pin "6") (pinfunction "b_6") (pintype "input"))
      (node (ref "LED12") (pin "6") (pinfunction "b_6") (pintype "input"))
      (node (ref "LED13") (pin "6") (pinfunction "b_6") (pintype "input"))
      (node (ref "LED14") (pin "6") (pinfunction "b_6") (pintype "input"))
      (node (ref "U15") (pin "1") (pinfunction "Q1_1") (pintype "input"))
    )
    (net (code "36") (name "Net-(LED11-c)") (class "Default")
      (node (ref "LED11") (pin "4") (pinfunction "c_4") (pintype "input"))
      (node (ref "LED12") (pin "4") (pinfunction "c_4") (pintype "input"))
      (node (ref "LED13") (pin "4") (pinfunction "c_4") (pintype "input"))
      (node (ref "LED14") (pin "4") (pinfunction "c_4") (pintype "input"))
      (node (ref "U15") (pin "2") (pinfunction "Q2_2") (pintype "input"))
    )
    (net (code "37") (name "Net-(LED11-d)") (class "Default")
      (node (ref "LED11") (pin "2") (pinfunction "d_2") (pintype "input"))
      (node (ref "LED12") (pin "2") (pinfunction "d_2") (pintype "input"))
      (node (ref "LED13") (pin "2") (pinfunction "d_2") (pintype "input"))
      (node (ref "LED14") (pin "2") (pinfunction "d_2") (pintype "input"))
      (node (ref "U15") (pin "3") (pinfunction "Q3_3") (pintype "input"))
    )
    (net (code "38") (name "Net-(LED11-dp)") (class "Default")
      (node (ref "LED11") (pin "5") (pinfunction "dp_5") (pintype "input"))
      (node (ref "LED12") (pin "5") (pinfunction "dp_5") (pintype "input"))
      (node (ref "LED13") (pin "5") (pinfunction "dp_5") (pintype "input"))
      (node (ref "LED14") (pin "5") (pinfunction "dp_5") (pintype "input"))
      (node (ref "U15") (pin "7") (pinfunction "Q7_7") (pintype "input"))
    )
    (net (code "39") (name "Net-(LED11-e)") (class "Default")
      (node (ref "LED11") (pin "1") (pinfunction "e_1") (pintype "input"))
      (node (ref "LED12") (pin "1") (pinfunction "e_1") (pintype "input"))
      (node (ref "LED13") (pin "1") (pinfunction "e_1") (pintype "input"))
      (node (ref "LED14") (pin "1") (pinfunction "e_1") (pintype "input"))
      (node (ref "U15") (pin "4") (pinfunction "Q4_4") (pintype "input"))
    )
    (net (code "40") (name "Net-(LED11-f)") (class "Default")
      (node (ref "LED11") (pin "9") (pinfunction "f_9") (pintype "input"))
      (node (ref "LED12") (pin "9") (pinfunction "f_9") (pintype "input"))
      (node (ref "LED13") (pin "9") (pinfunction "f_9") (pintype "input"))
      (node (ref "LED14") (pin "9") (pinfunction "f_9") (pintype "input"))
      (node (ref "U15") (pin "5") (pinfunction "Q5_5") (pintype "input"))
    )
    (net (code "41") (name "Net-(LED11-g)") (class "Default")
      (node (ref "LED11") (pin "10") (pinfunction "g_10") (pintype "input"))
      (node (ref "LED12") (pin "10") (pinfunction "g_10") (pintype "input"))
      (node (ref "LED13") (pin "10") (pinfunction "g_10") (pintype "input"))
      (node (ref "LED14") (pin "10") (pinfunction "g_10") (pintype "input"))
      (node (ref "U15") (pin "6") (pinfunction "Q6_6") (pintype "input"))
    )
    (net (code "42") (name "Net-(Q1-B)") (class "Default")
      (node (ref "Q1") (pin "1") (pinfunction "B_1") (pintype "input"))
      (node (ref "Q2") (pin "3") (pinfunction "C_3") (pintype "input"))
      (node (ref "R46") (pin "2") (pinfunction "2_2") (pintype "input"))
      (node (ref "U13") (pin "5") (pinfunction "IN2+_5") (pintype "input"))
    )
    (net (code "43") (name "Net-(Q3-B)") (class "Default")
      (node (ref "Q3") (pin "1") (pinfunction "B_1") (pintype "input"))
      (node (ref "Q4") (pin "3") (pinfunction "C_3") (pintype "input"))
      (node (ref "R47") (pin "2") (pinfunction "2_2") (pintype "input"))
      (node (ref "U13") (pin "3") (pinfunction "IN1+_3") (pintype "input"))
    )
    (net (code "44") (name "Net-(R10-Pad2)") (class "Default")
      (node (ref "R10") (pin "2") (pinfunction "2_2") (pintype "input"))
      (node (ref "R11") (pin "2") (pinfunction "2_2") (pintype "input"))
      (node (ref "R9") (pin "1") (pinfunction "1_1") (pintype "input"))
    )
    (net (code "45") (name "Net-(R19-Pad1)") (class "Default")
      (node (ref "R19") (pin "1") (pinfunction "1_1") (pintype "input"))
      (node (ref "R20") (pin "2") (pinfunction "2_2") (pintype "input"))
    )
    (net (code "46") (name "Net-(R20-Pad1)") (class "Default")
      (node (ref "R20") (pin "1") (pinfunction "1_1") (pintype "input"))
      (node (ref "R21") (pin "2") (pinfunction "2_2") (pintype "input"))
    )
    (net (code "47") (name "Net-(R22-Pad1)") (class "Default")
      (node (ref "R22") (pin "1") (pinfunction "1_1") (pintype "input"))
      (node (ref "R23") (pin "2") (pinfunction "2_2") (pintype "input"))
    )
    (net (code "48") (name "Net-(R23-Pad1)") (class "Default")
      (node (ref "R23") (pin "1") (pinfunction "1_1") (pintype "input"))
      (node (ref "R54") (pin "2") (pinfunction "2_2") (pintype "input"))
    )
    (net (code "49") (name "Net-(U1-PA2)") (class "Default")
      (node (ref "SW5") (pin "2") (pinfunction "2_2") (pintype "input"))
      (node (ref "U1") (pin "13") (pinfunction "PA2_13") (pintype "input"))
    )
    (net (code "50") (name "Net-(U1-PA3)") (class "Default")
      (node (ref "SW4") (pin "2") (pinfunction "2_2") (pintype "input"))
      (node (ref "U1") (pin "14") (pinfunction "PA3_14") (pintype "input"))
    )
    (net (code "51") (name "Net-(U1-PA13-SWD)") (class "Default")
      (node (ref "H8") (pin "1") (pinfunction "1_1") (pintype "unspecified"))
      (node (ref "U1") (pin "2") (pinfunction "PA13-SWD_2") (pintype "input"))
    )
    (net (code "52") (name "Net-(U1-PA14-SWC)") (class "Default")
      (node (ref "H9") (pin "1") (pinfunction "1_1") (pintype "unspecified"))
      (node (ref "U1") (pin "3") (pinfunction "PA14-SWC_3") (pintype "input"))
    )
    (net (code "53") (name "Net-(U1-PB6{slash}PF4-BOOT0)") (class "Default")
      (node (ref "R7") (pin "2") (pinfunction "2_2") (pintype "input"))
      (node (ref "U1") (pin "5") (pinfunction "PB6/PF4-BOOT0_5") (pintype "input"))
    )
    (net (code "54") (name "Net-(U1-PF0-OSCIN)") (class "Default")
      (node (ref "C1") (pin "1") (pinfunction "1_1") (pintype "input"))
      (node (ref "U1") (pin "8") (pinfunction "PF0-OSCIN_8") (pintype "input"))
      (node (ref "X1") (pin "1") (pinfunction "1_1") (pintype "input"))
    )
    (net (code "55") (name "Net-(U1-PF1-OSCOUT)") (class "Default")
      (node (ref "C2") (pin "2") (pinfunction "2_2") (pintype "input"))
      (node (ref "U1") (pin "9") (pinfunction "PF1-OSCOUT_9") (pintype "input"))
      (node (ref "X1") (pin "3") (pinfunction "3_3") (pintype "input"))
    )
    (net (code "56") (name "Net-(U1-PF2-NRST)") (class "Default")
      (node (ref "C3") (pin "2") (pinfunction "2_2") (pintype "input"))
      (node (ref "U1") (pin "10") (pinfunction "PF2-NRST_10") (pintype "input"))
    )
    (net (code "57") (name "Net-(U2A-IN1+)") (class "Default")
      (node (ref "C15") (pin "1") (pinfunction "1_1") (pintype "input"))
      (node (ref "R18") (pin "1") (pinfunction "1_1") (pintype "input"))
      (node (ref "R30") (pin "2") (pinfunction "2_2") (pintype "input"))
      (node (ref "U2") (pin "3") (pinfunction "IN1+_3") (pintype "input"))
    )
    (net (code "58") (name "Net-(U2A-IN1-)") (class "Default")
      (node (ref "R17") (pin "2") (pinfunction "2_2") (pintype "input"))
      (node (ref "U2") (pin "1") (pinfunction "OUT_1") (pintype "output"))
      (node (ref "U2") (pin "2") (pinfunction "IN1-_2") (pintype "input"))
    )
    (net (code "59") (name "Net-(U2B-IN2+)") (class "Default")
      (node (ref "R17") (pin "1") (pinfunction "1_1") (pintype "input"))
      (node (ref "R27") (pin "2") (pinfunction "2_2") (pintype "input"))
      (node (ref "U2") (pin "5") (pinfunction "IN2+_5") (pintype "input"))
    )
    (net (code "60") (name "Net-(U2B-IN2-)") (class "Default")
      (node (ref "R28") (pin "2") (pinfunction "2_2") (pintype "input"))
      (node (ref "R29") (pin "2") (pinfunction "2_2") (pintype "input"))
      (node (ref "U2") (pin "6") (pinfunction "IN2-_6") (pintype "input"))
    )
    (net (code "61") (name "Net-(U5-A)") (class "Default")
      (node (ref "C37") (pin "2") (pinfunction "2_2") (pintype "input"))
      (node (ref "U5") (pin "4") (pinfunction "A_4") (pintype "input"))
    )
    (net (code "62") (name "Net-(U5-B0)") (class "Default")
      (node (ref "R19") (pin "2") (pinfunction "2_2") (pintype "input"))
      (node (ref "R53") (pin "1") (pinfunction "1_1") (pintype "input"))
      (node (ref "U5") (pin "3") (pinfunction "B0_3") (pintype "input"))
    )
    (net (code "63") (name "Net-(U6-CHRG#)") (class "Default")
      (node (ref "R12") (pin "1") (pinfunction "1_1") (pintype "input"))
      (node (ref "U6") (pin "7") (pinfunction "CHRG#_7") (pintype "input"))
    )
    (net (code "64") (name "Net-(U6-PROG)") (class "Default")
      (node (ref "R9") (pin "2") (pinfunction "2_2") (pintype "input"))
      (node (ref "U6") (pin "2") (pinfunction "PROG_2") (pintype "input"))
    )
    (net (code "65") (name "Net-(U6-STDBY#)") (class "Default")
      (node (ref "R13") (pin "1") (pinfunction "1_1") (pintype "input"))
      (node (ref "U6") (pin "6") (pinfunction "STDBY#_6") (pintype "input"))
    )
    (net (code "66") (name "Net-(U7-CS)") (class "Default")
      (node (ref "R8") (pin "2") (pinfunction "2_2") (pintype "input"))
      (node (ref "U7") (pin "2") (pinfunction "CS_2") (pintype "input"))
    )
    (net (code "67") (name "Net-(U7-OC)") (class "Default")
      (node (ref "U7") (pin "3") (pinfunction "OC_3") (pintype "input"))
      (node (ref "U9") (pin "1") (pinfunction "G_1") (pintype "input"))
    )
    (net (code "68") (name "Net-(U7-OD)") (class "Default")
      (node (ref "U7") (pin "1") (pinfunction "OD_1") (pintype "input"))
      (node (ref "U8") (pin "1") (pinfunction "G_1") (pintype "input"))
    )
    (net (code "69") (name "Net-(U7-VCC)") (class "Default")
      (node (ref "C8") (pin "1") (pinfunction "1_1") (pintype "input"))
      (node (ref "R16") (pin "1") (pinfunction "1_1") (pintype "input"))
      (node (ref "U7") (pin "5") (pinfunction "VCC_5") (pintype "input"))
    )
    (net (code "70") (name "Net-(U8-D)") (class "Default")
      (node (ref "U8") (pin "3") (pinfunction "D_3") (pintype "input"))
      (node (ref "U9") (pin "3") (pinfunction "D_3") (pintype "input"))
    )
    (net (code "71") (name "Net-(U13A-IN1-)") (class "Default")
      (node (ref "C25") (pin "1") (pinfunction "1_1") (pintype "input"))
      (node (ref "R37") (pin "1") (pinfunction "1_1") (pintype "input"))
      (node (ref "R39") (pin "2") (pinfunction "2_2") (pintype "input"))
      (node (ref "U13") (pin "2") (pinfunction "IN1-_2") (pintype "input"))
    )
    (net (code "72") (name "Net-(U13A-OUT)") (class "Default")
      (node (ref "C25") (pin "2") (pinfunction "2_2") (pintype "input"))
      (node (ref "R37") (pin "2") (pinfunction "2_2") (pintype "input"))
      (node (ref "R45") (pin "1") (pinfunction "1_1") (pintype "input"))
      (node (ref "U13") (pin "1") (pinfunction "OUT_1") (pintype "output"))
    )
    (net (code "73") (name "Net-(U13B-IN2-)") (class "Default")
      (node (ref "C26") (pin "1") (pinfunction "1_1") (pintype "input"))
      (node (ref "R38") (pin "1") (pinfunction "1_1") (pintype "input"))
      (node (ref "R39") (pin "1") (pinfunction "1_1") (pintype "input"))
      (node (ref "U13") (pin "6") (pinfunction "IN2-_6") (pintype "input"))
    )
    (net (code "74") (name "Net-(U13B-OUT2)") (class "Default")
      (node (ref "C26") (pin "2") (pinfunction "2_2") (pintype "input"))
      (node (ref "R38") (pin "2") (pinfunction "2_2") (pintype "input"))
      (node (ref "R43") (pin "1") (pinfunction "1_1") (pintype "input"))
      (node (ref "U13") (pin "7") (pinfunction "OUT2_7") (pintype "output"))
    )
    (net (code "75") (name "Net-(U14A-IN1+)") (class "Default")
      (node (ref "R44") (pin "1") (pinfunction "1_1") (pintype "input"))
      (node (ref "R45") (pin "2") (pinfunction "2_2") (pintype "input"))
      (node (ref "U14") (pin "3") (pinfunction "IN1+_3") (pintype "input"))
    )
    (net (code "76") (name "Net-(U14A-IN1-)") (class "Default")
      (node (ref "R42") (pin "1") (pinfunction "1_1") (pintype "input"))
      (node (ref "R43") (pin "2") (pinfunction "2_2") (pintype "input"))
      (node (ref "U14") (pin "2") (pinfunction "IN1-_2") (pintype "input"))
    )
    (net (code "77") (name "Net-(U14A-OUT)") (class "Default")
      (node (ref "R42") (pin "2") (pinfunction "2_2") (pintype "input"))
      (node (ref "R53") (pin "2") (pinfunction "2_2") (pintype "input"))
      (node (ref "U14") (pin "1") (pinfunction "OUT_1") (pintype "output"))
      (node (ref "U5") (pin "1") (pinfunction "B1_1") (pintype "input"))
    )
    (net (code "78") (name "Net-(U14B-IN2+)") (class "Default")
      (node (ref "C37") (pin "1") (pinfunction "1_1") (pintype "input"))
      (node (ref "R56") (pin "2") (pinfunction "2_2") (pintype "input"))
      (node (ref "R57") (pin "1") (pinfunction "1_1") (pintype "input"))
      (node (ref "U14") (pin "5") (pinfunction "IN2+_5") (pintype "input"))
    )
    (net (code "79") (name "Net-(U14B-IN2-)") (class "Default")
      (node (ref "C36") (pin "1") (pinfunction "1_1") (pintype "input"))
      (node (ref "R22") (pin "2") (pinfunction "2_2") (pintype "input"))
      (node (ref "R55") (pin "1") (pinfunction "1_1") (pintype "input"))
      (node (ref "U14") (pin "6") (pinfunction "IN2-_6") (pintype "input"))
    )
    (net (code "80") (name "Net-(U15-Q7&apos;)") (class "Default")
      (node (ref "U15") (pin "9") (pinfunction "Q7&apos;_9") (pintype "input"))
      (node (ref "U16") (pin "14") (pinfunction "SER_14") (pintype "input"))
    )
    (net (code "81") (name "Net-(U16-Q0)") (class "Default")
      (node (ref "R3") (pin "1") (pinfunction "1_1") (pintype "input"))
      (node (ref "U16") (pin "15") (pinfunction "Q0_15") (pintype "input"))
    )
    (net (code "82") (name "Net-(U16-Q1)") (class "Default")
      (node (ref "LED11") (pin "3") (pinfunction "G1_3") (pintype "input"))
      (node (ref "U16") (pin "1") (pinfunction "Q1_1") (pintype "input"))
    )
    (net (code "83") (name "Net-(U16-Q2)") (class "Default")
      (node (ref "LED12") (pin "3") (pinfunction "G1_3") (pintype "input"))
      (node (ref "U16") (pin "2") (pinfunction "Q2_2") (pintype "input"))
    )
    (net (code "84") (name "Net-(U16-Q3)") (class "Default")
      (node (ref "LED13") (pin "3") (pinfunction "G1_3") (pintype "input"))
      (node (ref "U16") (pin "3") (pinfunction "Q3_3") (pintype "input"))
    )
    (net (code "85") (name "Net-(U16-Q4)") (class "Default")
      (node (ref "LED14") (pin "3") (pinfunction "G1_3") (pintype "input"))
      (node (ref "U16") (pin "4") (pinfunction "Q4_4") (pintype "input"))
    )
    (net (code "86") (name "Net-(U16-Q5)") (class "Default")
      (node (ref "R4") (pin "1") (pinfunction "1_1") (pintype "input"))
      (node (ref "U16") (pin "5") (pinfunction "Q5_5") (pintype "input"))
    )
    (net (code "87") (name "Net-(U16-Q6)") (class "Default")
      (node (ref "R5") (pin "1") (pinfunction "1_1") (pintype "input"))
      (node (ref "U16") (pin "6") (pinfunction "Q6_6") (pintype "input"))
    )
    (net (code "88") (name "Net-(U16-Q7)") (class "Default")
      (node (ref "R6") (pin "1") (pinfunction "1_1") (pintype "input"))
      (node (ref "U16") (pin "7") (pinfunction "Q7_7") (pintype "input"))
    )
    (net (code "89") (name "Net-(USB1-CC1)") (class "Default")
      (node (ref "R14") (pin "2") (pinfunction "2_2") (pintype "input"))
      (node (ref "USB1") (pin "4") (pinfunction "CC1_4") (pintype "input"))
    )
    (net (code "90") (name "Net-(USB1-CC2)") (class "Default")
      (node (ref "R15") (pin "2") (pinfunction "2_2") (pintype "input"))
      (node (ref "USB1") (pin "10") (pinfunction "CC2_10") (pintype "input"))
    )
    (net (code "91") (name "VCC") (class "Default")
      (node (ref "C12") (pin "2") (pinfunction "2_2") (pintype "input"))
      (node (ref "C9") (pin "2") (pinfunction "2_2") (pintype "input"))
      (node (ref "R18") (pin "2") (pinfunction "2_2") (pintype "input"))
      (node (ref "SW1") (pin "1") (pinfunction "1_1") (pintype "input"))
      (node (ref "U15") (pin "10") (pinfunction "NC_10") (pintype "input"))
      (node (ref "U15") (pin "16") (pinfunction "VDD_16") (pintype "input"))
      (node (ref "U16") (pin "10") (pinfunction "NC_10") (pintype "input"))
      (node (ref "U16") (pin "16") (pinfunction "VDD_16") (pintype "input"))
      (node (ref "U2") (pin "8") (pinfunction "VCC_8") (pintype "input"))
      (node (ref "U4") (pin "3") (pinfunction "VIN_3") (pintype "input"))
    )
    (net (code "92") (name "unconnected-(LED11-G1-Pad8)") (class "Default")
      (node (ref "LED11") (pin "8") (pinfunction "G1_8") (pintype "input"))
    )
    (net (code "93") (name "unconnected-(LED12-G1-Pad8)") (class "Default")
      (node (ref "LED12") (pin "8") (pinfunction "G1_8") (pintype "input"))
    )
    (net (code "94") (name "unconnected-(LED13-G1-Pad8)") (class "Default")
      (node (ref "LED13") (pin "8") (pinfunction "G1_8") (pintype "input"))
    )
    (net (code "95") (name "unconnected-(LED14-G1-Pad8)") (class "Default")
      (node (ref "LED14") (pin "8") (pinfunction "G1_8") (pintype "input"))
    )
    (net (code "96") (name "unconnected-(Q1-E-Pad2)") (class "Default")
      (node (ref "Q1") (pin "2") (pinfunction "E_2") (pintype "input+no_connect"))
    )
    (net (code "97") (name "unconnected-(Q2-E-Pad2)") (class "Default")
      (node (ref "Q2") (pin "2") (pinfunction "E_2") (pintype "input+no_connect"))
    )
    (net (code "98") (name "unconnected-(Q3-E-Pad2)") (class "Default")
      (node (ref "Q3") (pin "2") (pinfunction "E_2") (pintype "input+no_connect"))
    )
    (net (code "99") (name "unconnected-(Q4-E-Pad2)") (class "Default")
      (node (ref "Q4") (pin "2") (pinfunction "E_2") (pintype "input+no_connect"))
    )
    (net (code "100") (name "unconnected-(U1-PA6-Pad6)") (class "Default")
      (node (ref "U1") (pin "6") (pinfunction "PA6_6") (pintype "input"))
    )
    (net (code "101") (name "unconnected-(U1-PB1-Pad19)") (class "Default")
      (node (ref "U1") (pin "19") (pinfunction "PB1_19") (pintype "input"))
    )
    (net (code "102") (name "unconnected-(U1-PB2-Pad18)") (class "Default")
      (node (ref "U1") (pin "18") (pinfunction "PB2_18") (pintype "input"))
    )
    (net (code "103") (name "unconnected-(U7-TD-Pad4)") (class "Default")
      (node (ref "U7") (pin "4") (pinfunction "TD_4") (pintype "input"))
    )
    (net (code "104") (name "unconnected-(U16-Q7&apos;-Pad9)") (class "Default")
      (node (ref "U16") (pin "9") (pinfunction "Q7&apos;_9") (pintype "input"))
    )
    (net (code "105") (name "unconnected-(USB1-DN1-Pad7)") (class "Default")
      (node (ref "USB1") (pin "7") (pinfunction "DN1_7") (pintype "input"))
    )
    (net (code "106") (name "unconnected-(USB1-DN2-Pad5)") (class "Default")
      (node (ref "USB1") (pin "5") (pinfunction "DN2_5") (pintype "input"))
    )
    (net (code "107") (name "unconnected-(USB1-DP1-Pad6)") (class "Default")
      (node (ref "USB1") (pin "6") (pinfunction "DP1_6") (pintype "input"))
    )
    (net (code "108") (name "unconnected-(USB1-DP2-Pad8)") (class "Default")
      (node (ref "USB1") (pin "8") (pinfunction "DP2_8") (pintype "input"))
    )
    (net (code "109") (name "unconnected-(USB1-SBU1-Pad9)") (class "Default")
      (node (ref "USB1") (pin "9") (pinfunction "SBU1_9") (pintype "input"))
    )
    (net (code "110") (name "unconnected-(USB1-SBU2-Pad3)") (class "Default")
      (node (ref "USB1") (pin "3") (pinfunction "SBU2_3") (pintype "input"))
    )
  )
)
